# Autopilot.net
KiCad netlist of a schematic drawn in EAGLE
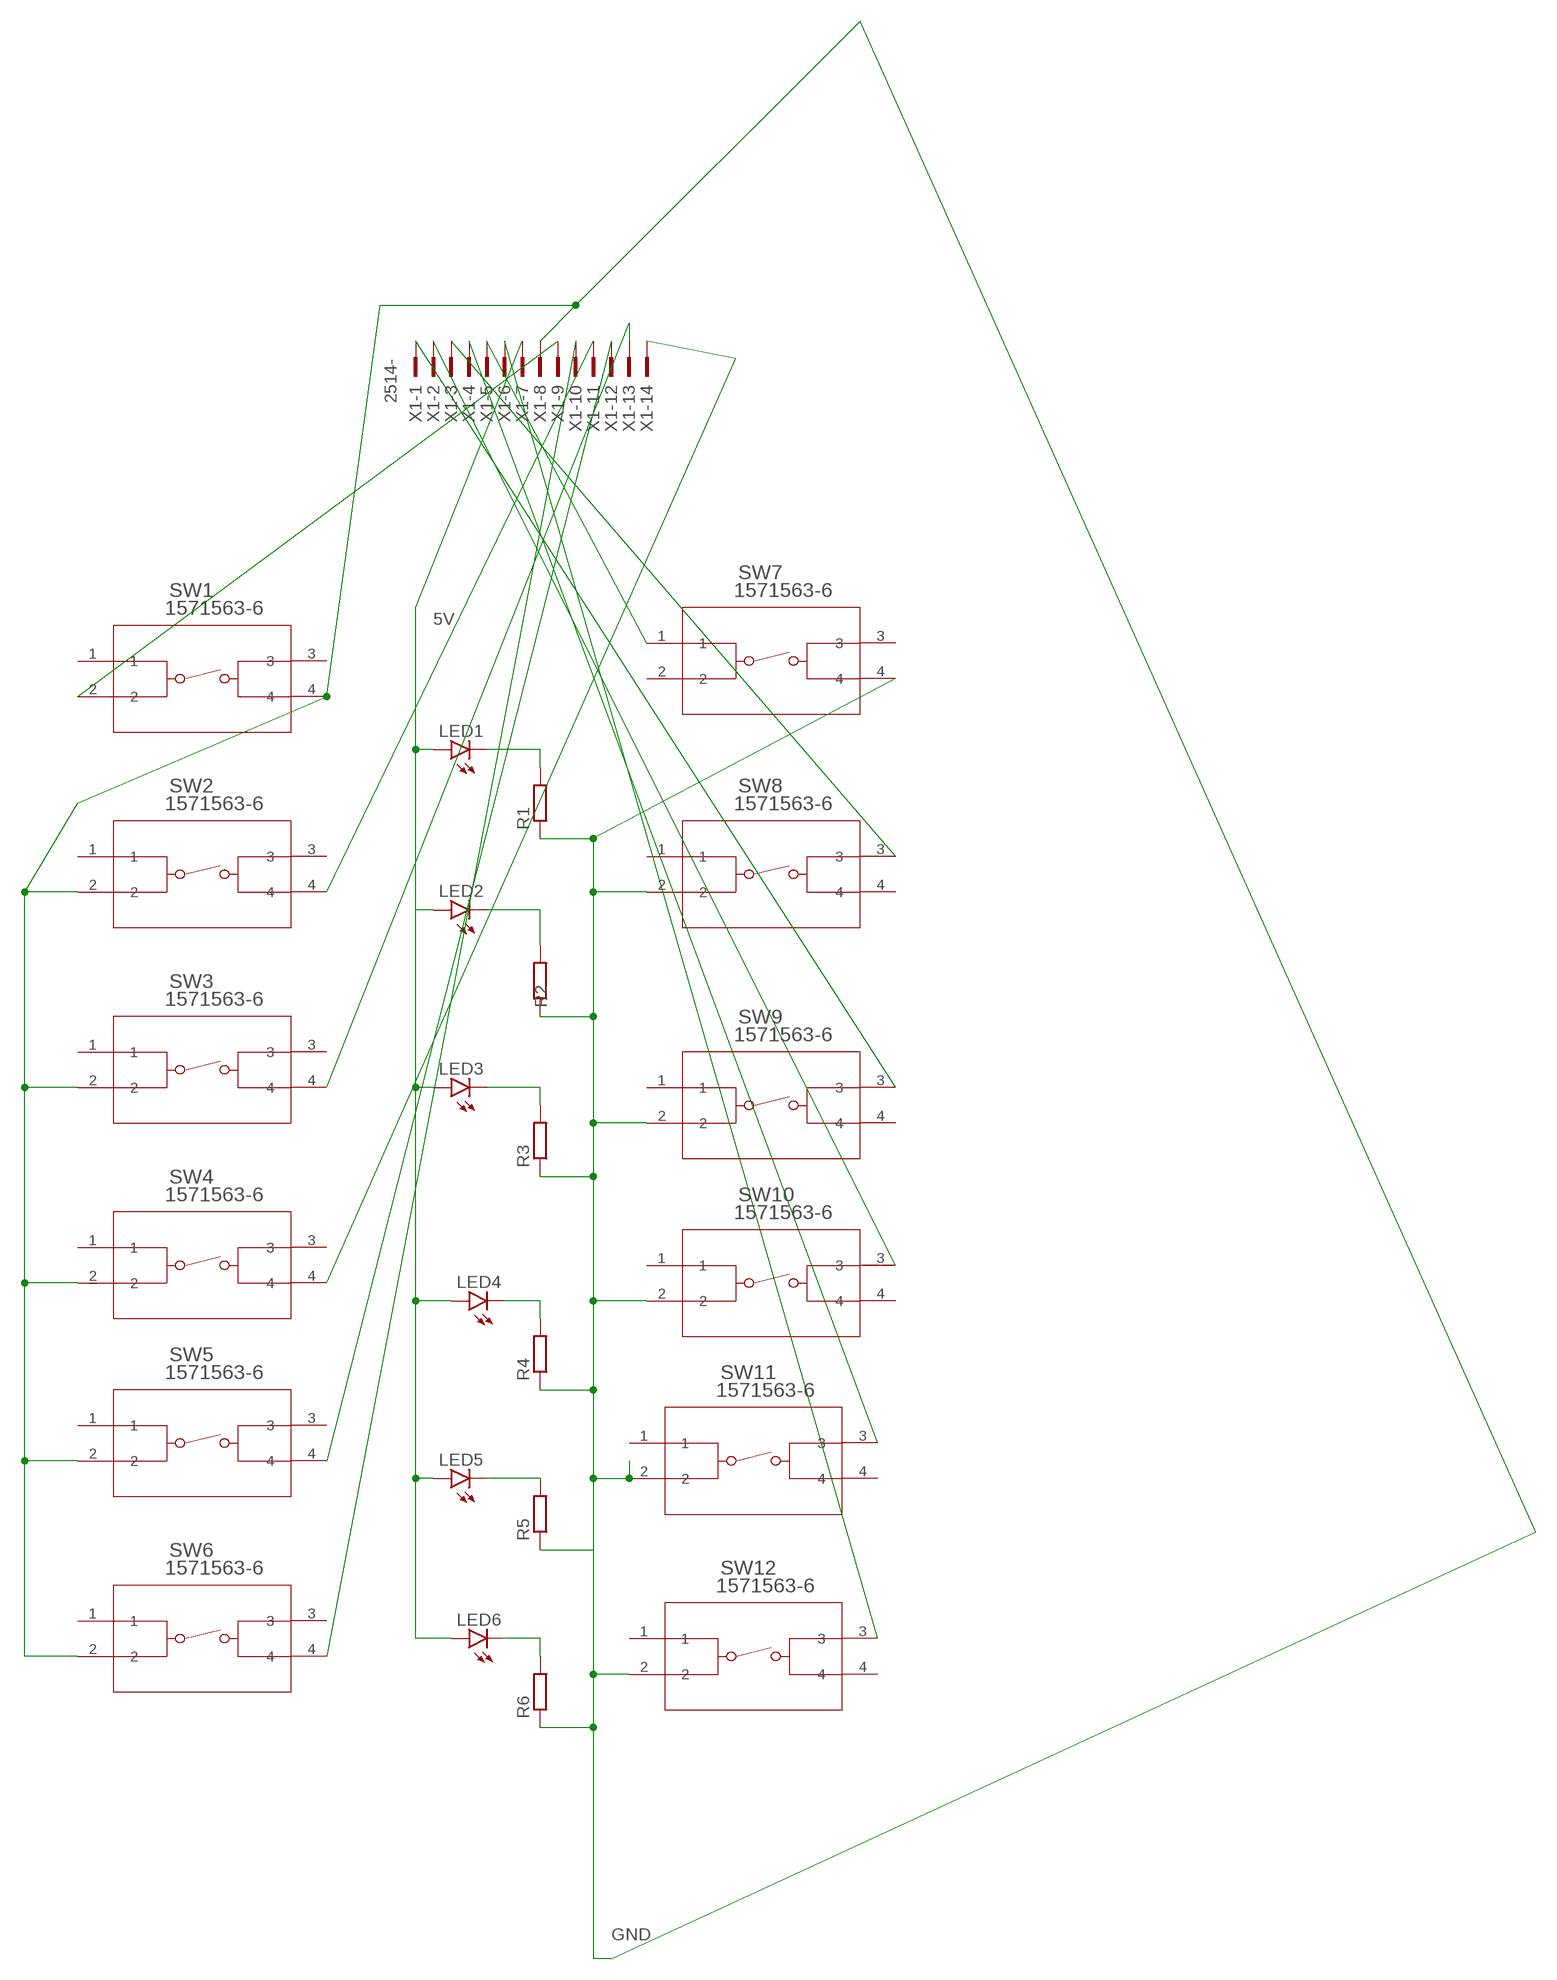
[diagram p0: schematic, sheet 1]

(export (version "E")
  (design (tool "Eeschema 10.0.6"))
  (components
    (comp (ref "LED1")
      (value "LEDCHIPLED_1206")
      (footprint "eagle-import:CHIPLED_1206")
      (libsource (lib "eagle-import") (part "LEDCHIPLED_1206"))
    )
    (comp (ref "LED2")
      (value "LEDCHIPLED_1206")
      (footprint "eagle-import:CHIPLED_1206")
      (libsource (lib "eagle-import") (part "LEDCHIPLED_1206"))
    )
    (comp (ref "LED3")
      (value "LEDCHIPLED_1206")
      (footprint "eagle-import:CHIPLED_1206")
      (libsource (lib "eagle-import") (part "LEDCHIPLED_1206"))
    )
    (comp (ref "LED4")
      (value "LEDCHIPLED_1206")
      (footprint "eagle-import:CHIPLED_1206")
      (libsource (lib "eagle-import") (part "LEDCHIPLED_1206"))
    )
    (comp (ref "LED5")
      (value "LEDCHIPLED_1206")
      (footprint "eagle-import:CHIPLED_1206")
      (libsource (lib "eagle-import") (part "LEDCHIPLED_1206"))
    )
    (comp (ref "LED6")
      (value "LEDCHIPLED_1206")
      (footprint "eagle-import:CHIPLED_1206")
      (libsource (lib "eagle-import") (part "LEDCHIPLED_1206"))
    )
    (comp (ref "R1")
      (value "R-EU_R1206")
      (footprint "eagle-import:R1206")
      (libsource (lib "eagle-import") (part "R-EU_R1206"))
    )
    (comp (ref "R2")
      (value "R-EU_R1206")
      (footprint "eagle-import:R1206")
      (libsource (lib "eagle-import") (part "R-EU_R1206"))
    )
    (comp (ref "R3")
      (value "R-EU_R1206")
      (footprint "eagle-import:R1206")
      (libsource (lib "eagle-import") (part "R-EU_R1206"))
    )
    (comp (ref "R4")
      (value "R-EU_R1206")
      (footprint "eagle-import:R1206")
      (libsource (lib "eagle-import") (part "R-EU_R1206"))
    )
    (comp (ref "R5")
      (value "R-EU_R1206")
      (footprint "eagle-import:R1206")
      (libsource (lib "eagle-import") (part "R-EU_R1206"))
    )
    (comp (ref "R6")
      (value "R-EU_R1206")
      (footprint "eagle-import:R1206")
      (libsource (lib "eagle-import") (part "R-EU_R1206"))
    )
    (comp (ref "SW1")
      (value "1571563-6")
      (footprint "eagle-import:SW4_1437565-E")
      (fields (field (name "COPYRIGHT") "Copyright (C) 2016 Accelerated Designs. All rights reserved"))
      (libsource (lib "eagle-import") (part "1571563-6"))
    )
    (comp (ref "SW2")
      (value "1571563-6")
      (footprint "eagle-import:SW4_1437565-E")
      (fields (field (name "COPYRIGHT") "Copyright (C) 2016 Accelerated Designs. All rights reserved"))
      (libsource (lib "eagle-import") (part "1571563-6"))
    )
    (comp (ref "SW3")
      (value "1571563-6")
      (footprint "eagle-import:SW4_1437565-E")
      (fields (field (name "COPYRIGHT") "Copyright (C) 2016 Accelerated Designs. All rights reserved"))
      (libsource (lib "eagle-import") (part "1571563-6"))
    )
    (comp (ref "SW4")
      (value "1571563-6")
      (footprint "eagle-import:SW4_1437565-E")
      (fields (field (name "COPYRIGHT") "Copyright (C) 2016 Accelerated Designs. All rights reserved"))
      (libsource (lib "eagle-import") (part "1571563-6"))
    )
    (comp (ref "SW5")
      (value "1571563-6")
      (footprint "eagle-import:SW4_1437565-E")
      (fields (field (name "COPYRIGHT") "Copyright (C) 2016 Accelerated Designs. All rights reserved"))
      (libsource (lib "eagle-import") (part "1571563-6"))
    )
    (comp (ref "SW6")
      (value "1571563-6")
      (footprint "eagle-import:SW4_1437565-E")
      (fields (field (name "COPYRIGHT") "Copyright (C) 2016 Accelerated Designs. All rights reserved"))
      (libsource (lib "eagle-import") (part "1571563-6"))
    )
    (comp (ref "SW7")
      (value "1571563-6")
      (footprint "eagle-import:SW4_1437565-E")
      (fields (field (name "COPYRIGHT") "Copyright (C) 2016 Accelerated Designs. All rights reserved"))
      (libsource (lib "eagle-import") (part "1571563-6"))
    )
    (comp (ref "SW8")
      (value "1571563-6")
      (footprint "eagle-import:SW4_1437565-E")
      (fields (field (name "COPYRIGHT") "Copyright (C) 2016 Accelerated Designs. All rights reserved"))
      (libsource (lib "eagle-import") (part "1571563-6"))
    )
    (comp (ref "SW9")
      (value "1571563-6")
      (footprint "eagle-import:SW4_1437565-E")
      (fields (field (name "COPYRIGHT") "Copyright (C) 2016 Accelerated Designs. All rights reserved"))
      (libsource (lib "eagle-import") (part "1571563-6"))
    )
    (comp (ref "SW10")
      (value "1571563-6")
      (footprint "eagle-import:SW4_1437565-E")
      (fields (field (name "COPYRIGHT") "Copyright (C) 2016 Accelerated Designs. All rights reserved"))
      (libsource (lib "eagle-import") (part "1571563-6"))
    )
    (comp (ref "SW11")
      (value "1571563-6")
      (footprint "eagle-import:SW4_1437565-E")
      (fields (field (name "COPYRIGHT") "Copyright (C) 2016 Accelerated Designs. All rights reserved"))
      (libsource (lib "eagle-import") (part "1571563-6"))
    )
    (comp (ref "SW12")
      (value "1571563-6")
      (footprint "eagle-import:SW4_1437565-E")
      (fields (field (name "COPYRIGHT") "Copyright (C) 2016 Accelerated Designs. All rights reserved"))
      (libsource (lib "eagle-import") (part "1571563-6"))
    )
    (comp (ref "X1")
      (value "2514-")
      (footprint "eagle-import:PAK100_2500-14")
      (libsource (lib "eagle-import") (part "2514-"))
    )
  )
  (nets
    (net (code "1") (name "/5V") (class "Default")
      (node (ref "LED1") (pin "A") (pinfunction "A_A") (pintype "passive"))
      (node (ref "LED2") (pin "A") (pinfunction "A_A") (pintype "passive"))
      (node (ref "LED3") (pin "A") (pinfunction "A_A") (pintype "passive"))
      (node (ref "LED4") (pin "A") (pinfunction "A_A") (pintype "passive"))
      (node (ref "LED5") (pin "A") (pinfunction "A_A") (pintype "passive"))
      (node (ref "LED6") (pin "A") (pinfunction "A_A") (pintype "passive"))
      (node (ref "X1") (pin "7") (pinfunction "KL_7") (pintype "passive"))
    )
    (net (code "2") (name "/GND") (class "Default")
      (node (ref "R1") (pin "1") (pinfunction "1_1") (pintype "passive"))
      (node (ref "R2") (pin "1") (pinfunction "1_1") (pintype "passive"))
      (node (ref "R3") (pin "1") (pinfunction "1_1") (pintype "passive"))
      (node (ref "R4") (pin "1") (pinfunction "1_1") (pintype "passive"))
      (node (ref "R5") (pin "1") (pinfunction "1_1") (pintype "passive"))
      (node (ref "R6") (pin "1") (pinfunction "1_1") (pintype "passive"))
      (node (ref "SW1") (pin "4") (pinfunction "4_4") (pintype "passive"))
      (node (ref "SW10") (pin "2") (pinfunction "2_2") (pintype "passive"))
      (node (ref "SW11") (pin "2") (pinfunction "2_2") (pintype "passive"))
      (node (ref "SW12") (pin "2") (pinfunction "2_2") (pintype "passive"))
      (node (ref "SW2") (pin "2") (pinfunction "2_2") (pintype "passive"))
      (node (ref "SW3") (pin "2") (pinfunction "2_2") (pintype "passive"))
      (node (ref "SW4") (pin "2") (pinfunction "2_2") (pintype "passive"))
      (node (ref "SW5") (pin "2") (pinfunction "2_2") (pintype "passive"))
      (node (ref "SW6") (pin "2") (pinfunction "2_2") (pintype "passive"))
      (node (ref "SW7") (pin "4") (pinfunction "4_4") (pintype "passive"))
      (node (ref "SW8") (pin "2") (pinfunction "2_2") (pintype "passive"))
      (node (ref "SW9") (pin "2") (pinfunction "2_2") (pintype "passive"))
      (node (ref "X1") (pin "8") (pinfunction "KL_8") (pintype "passive"))
    )
    (net (code "3") (name "Net-(LED1-PadC)") (class "Default")
      (node (ref "LED1") (pin "C") (pinfunction "C_C") (pintype "passive"))
      (node (ref "R1") (pin "2") (pinfunction "2_2") (pintype "passive"))
    )
    (net (code "4") (name "Net-(LED2-PadC)") (class "Default")
      (node (ref "LED2") (pin "C") (pinfunction "C_C") (pintype "passive"))
      (node (ref "R2") (pin "2") (pinfunction "2_2") (pintype "passive"))
    )
    (net (code "5") (name "Net-(LED3-PadC)") (class "Default")
      (node (ref "LED3") (pin "C") (pinfunction "C_C") (pintype "passive"))
      (node (ref "R3") (pin "2") (pinfunction "2_2") (pintype "passive"))
    )
    (net (code "6") (name "Net-(LED4-PadC)") (class "Default")
      (node (ref "LED4") (pin "C") (pinfunction "C_C") (pintype "passive"))
      (node (ref "R4") (pin "2") (pinfunction "2_2") (pintype "passive"))
    )
    (net (code "7") (name "Net-(LED5-PadC)") (class "Default")
      (node (ref "LED5") (pin "C") (pinfunction "C_C") (pintype "passive"))
      (node (ref "R5") (pin "2") (pinfunction "2_2") (pintype "passive"))
    )
    (net (code "8") (name "Net-(LED6-PadC)") (class "Default")
      (node (ref "LED6") (pin "C") (pinfunction "C_C") (pintype "passive"))
      (node (ref "R6") (pin "2") (pinfunction "2_2") (pintype "passive"))
    )
    (net (code "9") (name "Net-(X1A-KL)") (class "Default")
      (node (ref "SW9") (pin "3") (pinfunction "3_3") (pintype "passive"))
      (node (ref "X1") (pin "1") (pinfunction "KL_1") (pintype "passive"))
    )
    (net (code "10") (name "Net-(X1B-KL)") (class "Default")
      (node (ref "SW6") (pin "4") (pinfunction "4_4") (pintype "passive"))
      (node (ref "X1") (pin "10") (pinfunction "KL_10") (pintype "passive"))
    )
    (net (code "11") (name "Net-(X1C-KL)") (class "Default")
      (node (ref "SW2") (pin "4") (pinfunction "4_4") (pintype "passive"))
      (node (ref "X1") (pin "11") (pinfunction "KL_11") (pintype "passive"))
    )
    (net (code "12") (name "Net-(X1D-KL)") (class "Default")
      (node (ref "SW5") (pin "4") (pinfunction "4_4") (pintype "passive"))
      (node (ref "X1") (pin "12") (pinfunction "KL_12") (pintype "passive"))
    )
    (net (code "13") (name "Net-(X1E-KL)") (class "Default")
      (node (ref "SW3") (pin "4") (pinfunction "4_4") (pintype "passive"))
      (node (ref "X1") (pin "13") (pinfunction "KL_13") (pintype "passive"))
    )
    (net (code "14") (name "Net-(X1F-KL)") (class "Default")
      (node (ref "SW4") (pin "4") (pinfunction "4_4") (pintype "passive"))
      (node (ref "X1") (pin "14") (pinfunction "KL_14") (pintype "passive"))
    )
    (net (code "15") (name "Net-(X1G-KL)") (class "Default")
      (node (ref "SW10") (pin "3") (pinfunction "3_3") (pintype "passive"))
      (node (ref "X1") (pin "2") (pinfunction "KL_2") (pintype "passive"))
    )
    (net (code "16") (name "Net-(X1H-KL)") (class "Default")
      (node (ref "SW8") (pin "3") (pinfunction "3_3") (pintype "passive"))
      (node (ref "X1") (pin "3") (pinfunction "KL_3") (pintype "passive"))
    )
    (net (code "17") (name "Net-(X1I-KL)") (class "Default")
      (node (ref "SW11") (pin "3") (pinfunction "3_3") (pintype "passive"))
      (node (ref "X1") (pin "4") (pinfunction "KL_4") (pintype "passive"))
    )
    (net (code "18") (name "Net-(X1J-KL)") (class "Default")
      (node (ref "SW7") (pin "1") (pinfunction "1_1") (pintype "passive"))
      (node (ref "X1") (pin "5") (pinfunction "KL_5") (pintype "passive"))
    )
    (net (code "19") (name "Net-(X1K-KL)") (class "Default")
      (node (ref "SW12") (pin "3") (pinfunction "3_3") (pintype "passive"))
      (node (ref "X1") (pin "6") (pinfunction "KL_6") (pintype "passive"))
    )
    (net (code "20") (name "Net-(X1N-KL)") (class "Default")
      (node (ref "SW1") (pin "2") (pinfunction "2_2") (pintype "passive"))
      (node (ref "X1") (pin "9") (pinfunction "KL_9") (pintype "passive"))
    )
    (net (code "21") (name "unconnected-(SW1-Pad1)") (class "Default")
      (node (ref "SW1") (pin "1") (pinfunction "1_1") (pintype "passive"))
    )
    (net (code "22") (name "unconnected-(SW1-Pad3)") (class "Default")
      (node (ref "SW1") (pin "3") (pinfunction "3_3") (pintype "passive"))
    )
    (net (code "23") (name "unconnected-(SW2-Pad1)") (class "Default")
      (node (ref "SW2") (pin "1") (pinfunction "1_1") (pintype "passive"))
    )
    (net (code "24") (name "unconnected-(SW2-Pad3)") (class "Default")
      (node (ref "SW2") (pin "3") (pinfunction "3_3") (pintype "passive"))
    )
    (net (code "25") (name "unconnected-(SW3-Pad1)") (class "Default")
      (node (ref "SW3") (pin "1") (pinfunction "1_1") (pintype "passive"))
    )
    (net (code "26") (name "unconnected-(SW3-Pad3)") (class "Default")
      (node (ref "SW3") (pin "3") (pinfunction "3_3") (pintype "passive"))
    )
    (net (code "27") (name "unconnected-(SW4-Pad1)") (class "Default")
      (node (ref "SW4") (pin "1") (pinfunction "1_1") (pintype "passive"))
    )
    (net (code "28") (name "unconnected-(SW4-Pad3)") (class "Default")
      (node (ref "SW4") (pin "3") (pinfunction "3_3") (pintype "passive"))
    )
    (net (code "29") (name "unconnected-(SW5-Pad1)") (class "Default")
      (node (ref "SW5") (pin "1") (pinfunction "1_1") (pintype "passive"))
    )
    (net (code "30") (name "unconnected-(SW5-Pad3)") (class "Default")
      (node (ref "SW5") (pin "3") (pinfunction "3_3") (pintype "passive"))
    )
    (net (code "31") (name "unconnected-(SW6-Pad1)") (class "Default")
      (node (ref "SW6") (pin "1") (pinfunction "1_1") (pintype "passive"))
    )
    (net (code "32") (name "unconnected-(SW6-Pad3)") (class "Default")
      (node (ref "SW6") (pin "3") (pinfunction "3_3") (pintype "passive"))
    )
    (net (code "33") (name "unconnected-(SW7-Pad2)") (class "Default")
      (node (ref "SW7") (pin "2") (pinfunction "2_2") (pintype "passive"))
    )
    (net (code "34") (name "unconnected-(SW7-Pad3)") (class "Default")
      (node (ref "SW7") (pin "3") (pinfunction "3_3") (pintype "passive"))
    )
    (net (code "35") (name "unconnected-(SW8-Pad1)") (class "Default")
      (node (ref "SW8") (pin "1") (pinfunction "1_1") (pintype "passive"))
    )
    (net (code "36") (name "unconnected-(SW8-Pad4)") (class "Default")
      (node (ref "SW8") (pin "4") (pinfunction "4_4") (pintype "passive"))
    )
    (net (code "37") (name "unconnected-(SW9-Pad1)") (class "Default")
      (node (ref "SW9") (pin "1") (pinfunction "1_1") (pintype "passive"))
    )
    (net (code "38") (name "unconnected-(SW9-Pad4)") (class "Default")
      (node (ref "SW9") (pin "4") (pinfunction "4_4") (pintype "passive"))
    )
    (net (code "39") (name "unconnected-(SW10-Pad1)") (class "Default")
      (node (ref "SW10") (pin "1") (pinfunction "1_1") (pintype "passive"))
    )
    (net (code "40") (name "unconnected-(SW10-Pad4)") (class "Default")
      (node (ref "SW10") (pin "4") (pinfunction "4_4") (pintype "passive"))
    )
    (net (code "41") (name "unconnected-(SW11-Pad1)") (class "Default")
      (node (ref "SW11") (pin "1") (pinfunction "1_1") (pintype "passive"))
    )
    (net (code "42") (name "unconnected-(SW11-Pad4)") (class "Default")
      (node (ref "SW11") (pin "4") (pinfunction "4_4") (pintype "passive"))
    )
    (net (code "43") (name "unconnected-(SW12-Pad1)") (class "Default")
      (node (ref "SW12") (pin "1") (pinfunction "1_1") (pintype "passive"))
    )
    (net (code "44") (name "unconnected-(SW12-Pad4)") (class "Default")
      (node (ref "SW12") (pin "4") (pinfunction "4_4") (pintype "passive"))
    )
  )
)
